# ADC_2CH.net
KiCad netlist of a schematic drawn in Altium Designer
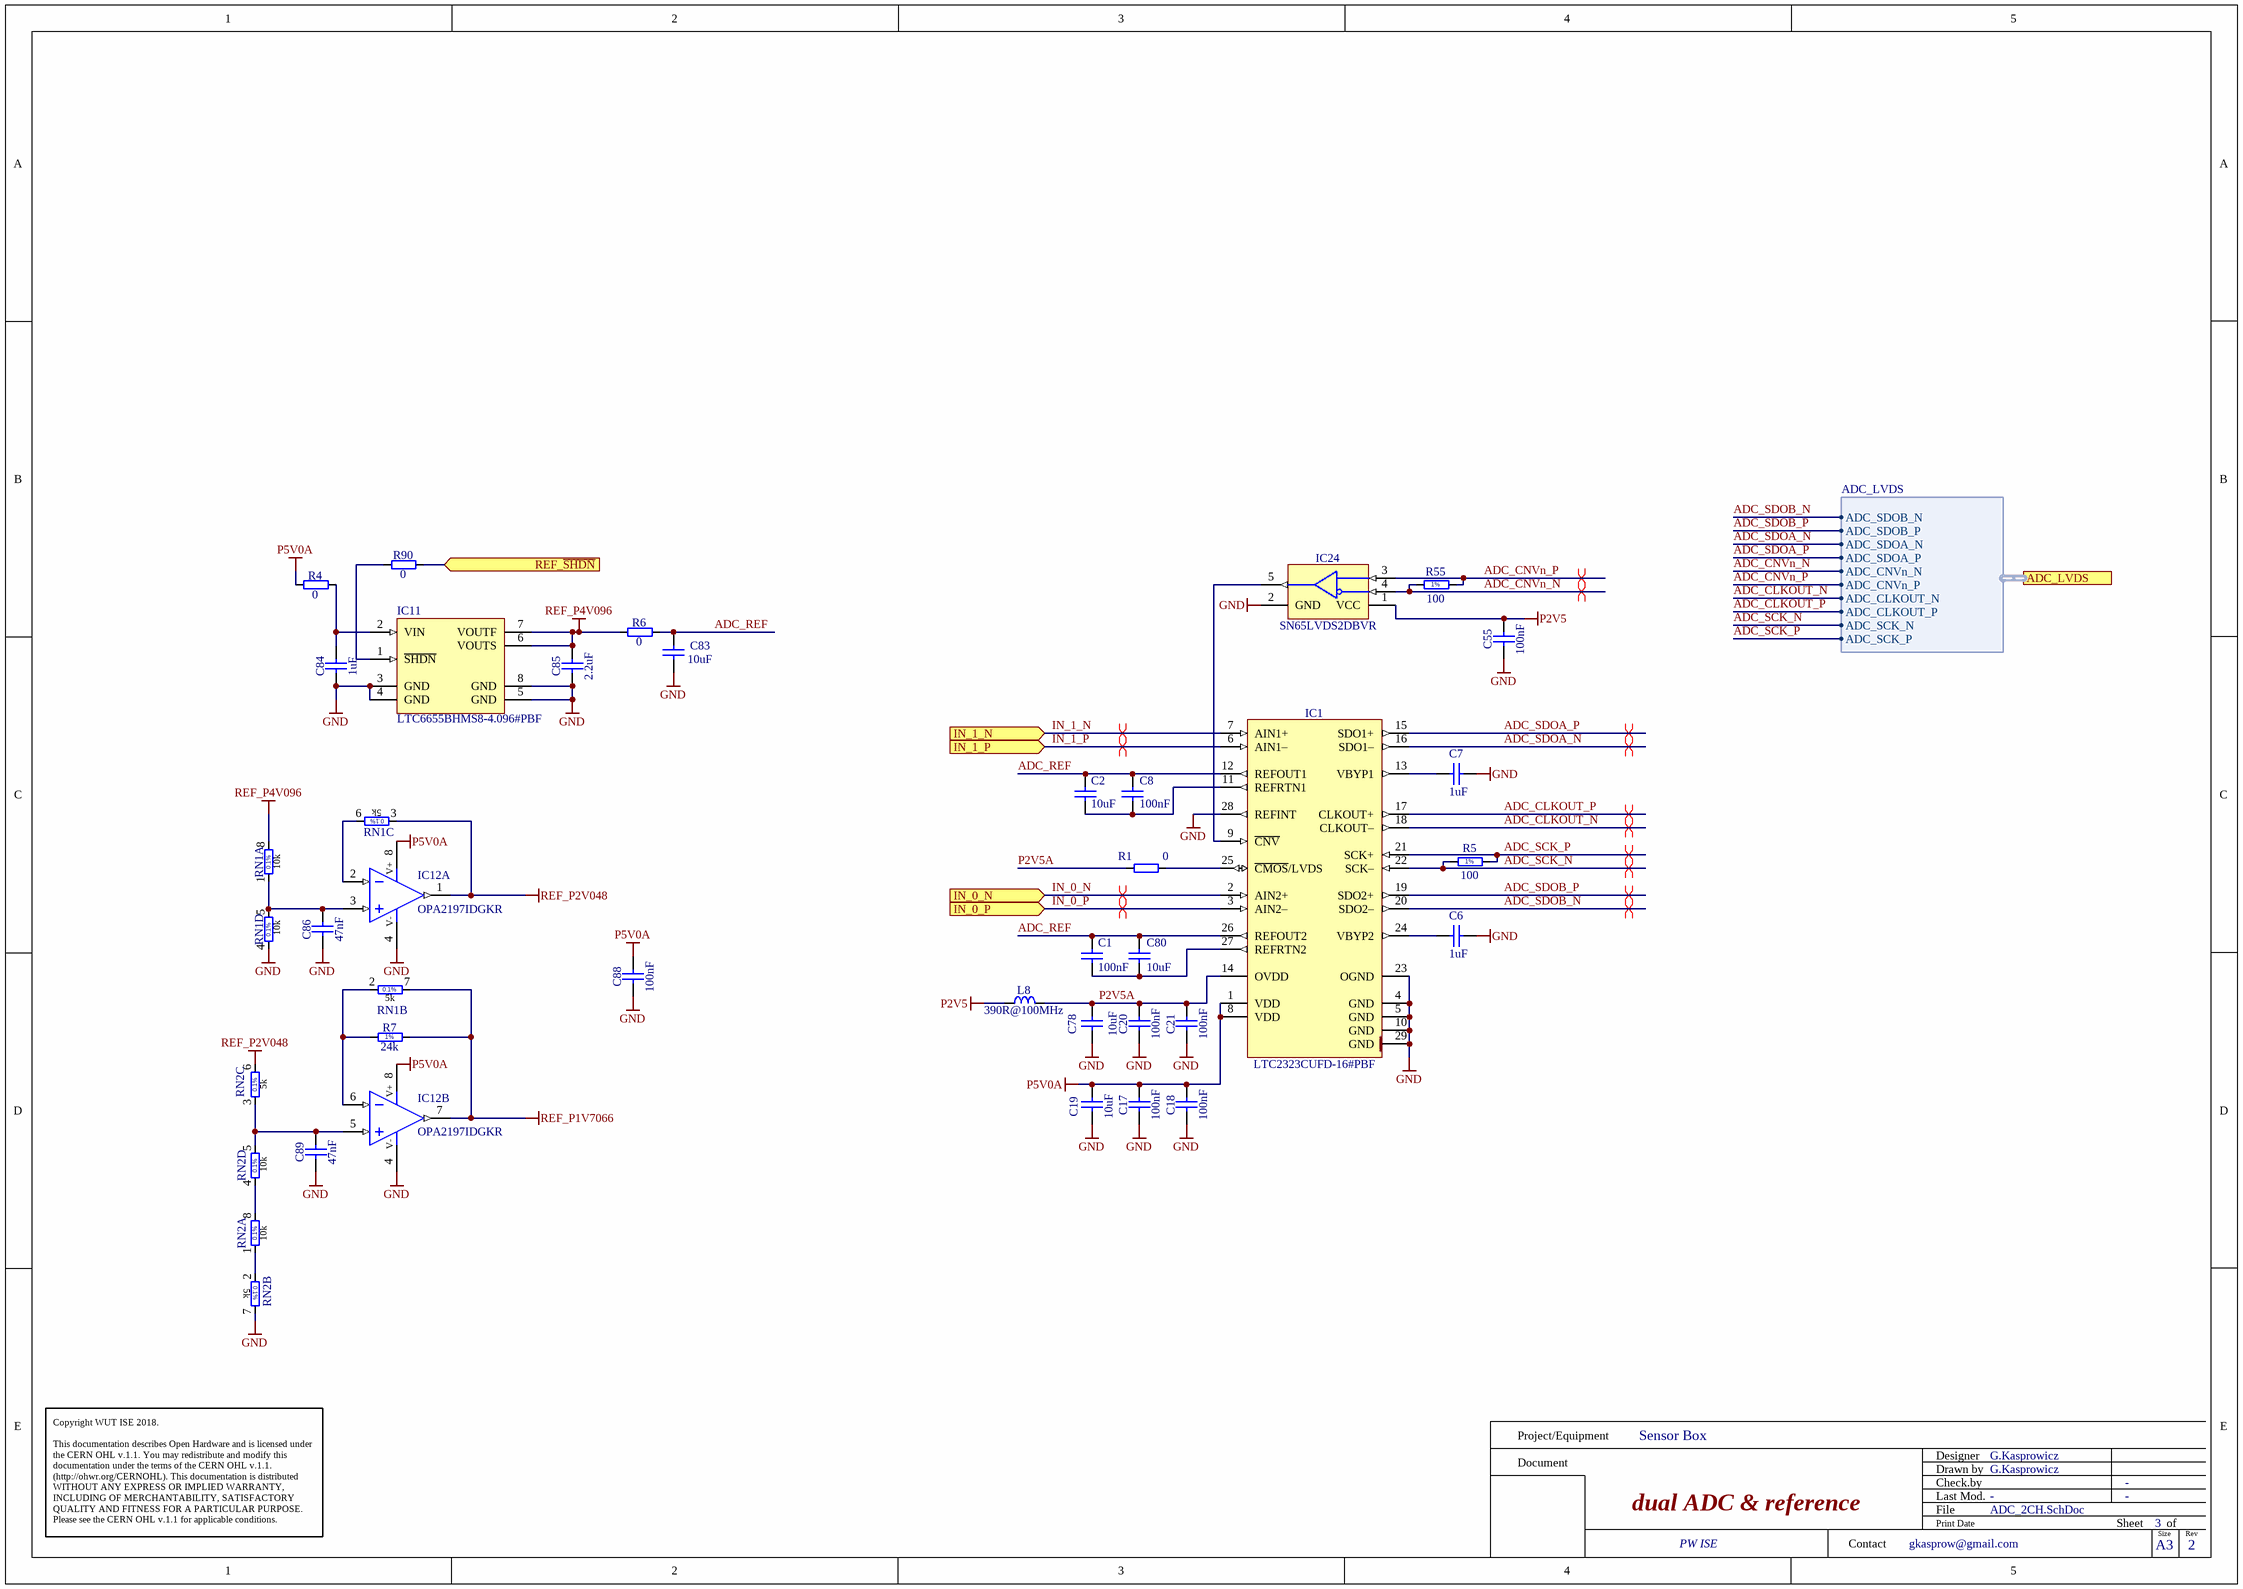
[diagram p0: ADC_2CH.SchDoc]

(export (version "E")
  (design (tool "Eeschema 10.0.6"))
  (components
    (comp (ref "C1")
      (value "100nF")
      (footprint "CAPC1608X87N")
      (description "Non-polarised capacitor")
      (fields
        (field (name "PART NUMBER") "CC0603_100NF_50V_10%_X7R")
        (field (name "VOLTAGE") "50V")
        (field (name "AUTHOR") "CERN DEM JLC")
      )
      (libsource (lib "Capacitors") (part "Capacitor - non polarized"))
    )
    (comp (ref "C2")
      (value "10uF")
      (footprint "CAPC2012X95N")
      (description "Non-polarised capacitor")
      (fields
        (field (name "PART NUMBER") "CC0805_10UF_25V_10%_X5R")
        (field (name "VOLTAGE") "25V")
        (field (name "AUTHOR") "CERN DEM JLC")
      )
      (libsource (lib "Capacitors") (part "Capacitor - non polarized"))
    )
    (comp (ref "C6")
      (value "1uF")
      (footprint "CAPC1608X87N")
      (description "Non-polarised capacitor")
      (fields
        (field (name "PART NUMBER") "CC0603_1UF_25V_10%_X7R")
        (field (name "VOLTAGE") "25V")
        (field (name "AUTHOR") "CERN DEM JLC")
      )
      (libsource (lib "Capacitors") (part "Capacitor - non polarized"))
    )
    (comp (ref "C7")
      (value "1uF")
      (footprint "CAPC1608X87N")
      (description "Non-polarised capacitor")
      (fields
        (field (name "PART NUMBER") "CC0603_1UF_25V_10%_X7R")
        (field (name "VOLTAGE") "25V")
        (field (name "AUTHOR") "CERN DEM JLC")
      )
      (libsource (lib "Capacitors") (part "Capacitor - non polarized"))
    )
    (comp (ref "C8")
      (value "100nF")
      (footprint "CAPC1608X87N")
      (description "Non-polarised capacitor")
      (fields
        (field (name "PART NUMBER") "CC0603_100NF_50V_10%_X7R")
        (field (name "VOLTAGE") "50V")
        (field (name "AUTHOR") "CERN DEM JLC")
      )
      (libsource (lib "Capacitors") (part "Capacitor - non polarized"))
    )
    (comp (ref "C17")
      (value "100nF")
      (footprint "CAPC1608X87N")
      (description "Non-polarised capacitor")
      (fields
        (field (name "PART NUMBER") "CC0603_100NF_50V_10%_X7R")
        (field (name "VOLTAGE") "50V")
        (field (name "AUTHOR") "CERN DEM JLC")
      )
      (libsource (lib "Capacitors") (part "Capacitor - non polarized"))
    )
    (comp (ref "C18")
      (value "100nF")
      (footprint "CAPC1608X87N")
      (description "Non-polarised capacitor")
      (fields
        (field (name "PART NUMBER") "CC0603_100NF_50V_10%_X7R")
        (field (name "VOLTAGE") "50V")
        (field (name "AUTHOR") "CERN DEM JLC")
      )
      (libsource (lib "Capacitors") (part "Capacitor - non polarized"))
    )
    (comp (ref "C19")
      (value "10uF")
      (footprint "CAPC2012X95N")
      (description "Non-polarised capacitor")
      (fields
        (field (name "PART NUMBER") "CC0805_10UF_25V_10%_X5R")
        (field (name "VOLTAGE") "25V")
        (field (name "AUTHOR") "CERN DEM JLC")
      )
      (libsource (lib "Capacitors") (part "Capacitor - non polarized"))
    )
    (comp (ref "C20")
      (value "100nF")
      (footprint "CAPC1608X87N")
      (description "Non-polarised capacitor")
      (fields
        (field (name "PART NUMBER") "CC0603_100NF_50V_10%_X7R")
        (field (name "VOLTAGE") "50V")
        (field (name "AUTHOR") "CERN DEM JLC")
      )
      (libsource (lib "Capacitors") (part "Capacitor - non polarized"))
    )
    (comp (ref "C21")
      (value "100nF")
      (footprint "CAPC1608X87N")
      (description "Non-polarised capacitor")
      (fields
        (field (name "PART NUMBER") "CC0603_100NF_50V_10%_X7R")
        (field (name "VOLTAGE") "50V")
        (field (name "AUTHOR") "CERN DEM JLC")
      )
      (libsource (lib "Capacitors") (part "Capacitor - non polarized"))
    )
    (comp (ref "C55")
      (value "100nF")
      (footprint "CAPC1608X87N")
      (description "Non-polarised capacitor")
      (fields
        (field (name "PART NUMBER") "CC0603_100NF_50V_10%_X7R")
        (field (name "VOLTAGE") "50V")
        (field (name "AUTHOR") "CERN DEM JLC")
      )
      (libsource (lib "Capacitors") (part "Capacitor - non polarized"))
    )
    (comp (ref "C78")
      (value "10uF")
      (footprint "CAPC2012X95N")
      (description "Non-polarised capacitor")
      (fields
        (field (name "PART NUMBER") "CC0805_10UF_25V_10%_X5R")
        (field (name "VOLTAGE") "25V")
        (field (name "AUTHOR") "CERN DEM JLC")
      )
      (libsource (lib "Capacitors") (part "Capacitor - non polarized"))
    )
    (comp (ref "C80")
      (value "10uF")
      (footprint "CAPC2012X95N")
      (description "Non-polarised capacitor")
      (fields
        (field (name "PART NUMBER") "CC0805_10UF_25V_10%_X5R")
        (field (name "VOLTAGE") "25V")
        (field (name "AUTHOR") "CERN DEM JLC")
      )
      (libsource (lib "Capacitors") (part "Capacitor - non polarized"))
    )
    (comp (ref "C83")
      (value "10uF")
      (footprint "CAPC2012X95N")
      (description "Non-polarised capacitor")
      (fields
        (field (name "PART NUMBER") "CC0805_10UF_25V_10%_X5R")
        (field (name "VOLTAGE") "25V")
        (field (name "AUTHOR") "CERN DEM JLC")
      )
      (libsource (lib "Capacitors") (part "Capacitor - non polarized"))
    )
    (comp (ref "C84")
      (value "1uF")
      (footprint "CAPC1608X87N")
      (description "Non-polarised capacitor")
      (fields
        (field (name "PART NUMBER") "CC0603_1UF_25V_10%_X7R")
        (field (name "VOLTAGE") "25V")
        (field (name "AUTHOR") "CERN DEM JLC")
      )
      (libsource (lib "Capacitors") (part "Capacitor - non polarized"))
    )
    (comp (ref "C85")
      (value "2.2uF")
      (footprint "CAPC1608X87N")
      (description "Non-polarised capacitor")
      (fields
        (field (name "PART NUMBER") "CC0603_2.2UF_16V_10%_X5R")
        (field (name "VOLTAGE") "16V")
        (field (name "AUTHOR") "CERN DEM JLC")
      )
      (libsource (lib "Capacitors") (part "Capacitor - non polarized"))
    )
    (comp (ref "C86")
      (value "47nF")
      (footprint "CAPC2012X135N")
      (description "Non-polarised capacitor")
      (fields
        (field (name "PART NUMBER") "CC0805_47NF_25V_5%_C0G")
        (field (name "VOLTAGE") "25V")
        (field (name "AUTHOR") "CERN DEM JLC")
      )
      (libsource (lib "Capacitors") (part "Capacitor - non polarized"))
    )
    (comp (ref "C88")
      (value "100nF")
      (footprint "CAPC1005X55N")
      (description "Non-polarised capacitor")
      (fields
        (field (name "PART NUMBER") "CC0402_100NF_16V_10%_X5R")
        (field (name "VOLTAGE") "16V")
        (field (name "AUTHOR") "CERN DEM JLC")
      )
      (libsource (lib "Capacitors") (part "Capacitor - non polarized"))
    )
    (comp (ref "C89")
      (value "47nF")
      (footprint "CAPC2012X135N")
      (description "Non-polarised capacitor")
      (fields
        (field (name "PART NUMBER") "CC0805_47NF_25V_5%_C0G")
        (field (name "VOLTAGE") "25V")
        (field (name "AUTHOR") "CERN DEM JLC")
      )
      (libsource (lib "Capacitors") (part "Capacitor - non polarized"))
    )
    (comp (ref "IC1")
      (value "LTC2323CUFD-16#PBF")
      (footprint "QFN50P400X500X80-29N-R275X375")
      (description "Dual, 16-Bit, 5Msps Differential Input ADC with Wide Input Common Mode Range")
      (fields (field (name "MANUFACTURER") "ANALOG DEVICES") (field (name "AUTHOR") "CERN DEM JMW"))
      (libsource (lib "ICs And Semiconductors") (part "LTC2323-16"))
    )
    (comp (ref "IC11")
      (value "LTC6655BHMS8-4.096#PBF")
      (footprint "SOP65P490X110-8N")
      (description "0.25ppm Noise, Low Drift Precision Buffered Voltage Reference")
      (fields (field (name "MANUFACTURER") "LINEAR TECHNOLOGY") (field (name "AUTHOR") "GK"))
      (libsource (lib "LIBRARY_SCH") (part "REF_LTC6655"))
    )
    (comp (ref "IC12")
      (value "OPA2197IDGKR")
      (footprint "SOP65P490X110-8N")
      (description "36-V, Precision, Rail-to-Rail Input Output, Low Offset Voltage Op Amp 8-VSSOP")
      (fields (field (name "MANUFACTURER") "TEXAS INSTRUMENTS") (field (name "AUTHOR") "GK"))
      (libsource (lib "LIBRARY_SCH") (part "OA_OPA2197IDGKR"))
    )
    (comp (ref "IC24")
      (value "SN65LVDS2DBVR")
      (footprint "SOT95P280X145-5N")
      (description "High-Speed Differential Line Receiver")
      (fields (field (name "MANUFACTURER") "TEXAS INSTRUMENTS") (field (name "AUTHOR") "CERN DEM JLC"))
      (libsource (lib "ICs And Semiconductors") (part "SN65LVDS2DBV"))
    )
    (comp (ref "L8")
      (value "390R@100MHz")
      (footprint "INDC1608X95N")
      (description "Inductor")
      (fields
        (field (name "PART NUMBER") "IND0603_TDK_MPZ1608R391A")
        (field (name "POWER") "1.2A")
        (field (name "AUTHOR") "CERN DEM JLC")
      )
      (libsource (lib "Inductors & Transformers") (part "Inductor"))
    )
    (comp (ref "R1")
      (value "0")
      (footprint "RESC1005X40N")
      (description "Resistor")
      (fields
        (field (name "PART NUMBER") "R0402_0R_JUMPER")
        (field (name "MANUFACTURER") "GENERIC")
        (field (name "AUTHOR") "CERN DEM JLC")
      )
      (libsource (lib "Resistors") (part "Resistor"))
    )
    (comp (ref "R4")
      (value "0")
      (footprint "RESC1005X40N")
      (description "Resistor")
      (fields
        (field (name "PART NUMBER") "R0402_0R_JUMPER")
        (field (name "MANUFACTURER") "GENERIC")
        (field (name "AUTHOR") "CERN DEM JLC")
      )
      (libsource (lib "Resistors") (part "Resistor"))
    )
    (comp (ref "R5")
      (value "100")
      (footprint "RESC1005X40N")
      (description "Resistor - 1%")
      (fields
        (field (name "PART NUMBER") "R0402_100R_1%_0.1W_100PPM")
        (field (name "POWER") "0.1W")
        (field (name "AUTHOR") "CERN DEM JLC")
      )
      (libsource (lib "Resistors") (part "Resistor - 1%"))
    )
    (comp (ref "R6")
      (value "0")
      (footprint "RESC1005X40N")
      (description "Resistor")
      (fields
        (field (name "PART NUMBER") "R0402_0R_JUMPER")
        (field (name "MANUFACTURER") "GENERIC")
        (field (name "AUTHOR") "CERN DEM JLC")
      )
      (libsource (lib "Resistors") (part "Resistor"))
    )
    (comp (ref "R7")
      (value "24k")
      (footprint "RESC1608X55N")
      (description "Resistor - 1%")
      (fields
        (field (name "PART NUMBER") "R0603_24K_1%_0.1W_100PPM")
        (field (name "POWER") "0.1W")
        (field (name "AUTHOR") "CERN DEM JLC")
      )
      (libsource (lib "Resistors") (part "Resistor - 1%"))
    )
    (comp (ref "R55")
      (value "100")
      (footprint "RESC1005X40N")
      (description "Resistor - 1%")
      (fields
        (field (name "PART NUMBER") "R0402_100R_1%_0.1W_100PPM")
        (field (name "POWER") "0.1W")
        (field (name "AUTHOR") "CERN DEM JLC")
      )
      (libsource (lib "Resistors") (part "Resistor - 1%"))
    )
    (comp (ref "R90")
      (value "0")
      (footprint "RESC1005X40N")
      (description "Resistor")
      (fields
        (field (name "PART NUMBER") "R0402_0R_JUMPER")
        (field (name "MANUFACTURER") "GENERIC")
        (field (name "AUTHOR") "CERN DEM JLC")
      )
      (libsource (lib "Resistors") (part "Resistor"))
    )
    (comp (ref "RN1")
      (value "10k 5K 5K 10K")
      (footprint "SOIC127P600X175-8N")
      (description "DIL8 Resistor Network 4 Resistors 10k-5k-5k-10k 0.1%")
      (fields
        (field (name "PART NUMBER") "RN_10K_5K_VISHAY_AORN2-1AT3")
        (field (name "POWER") "4x0.1W")
        (field (name "AUTHOR") "CERN DEM JLC")
      )
      (libsource (lib "Resistors") (part "RN DIL8_4xR_10k-5k-5k-10k_0.1%"))
    )
    (comp (ref "RN2")
      (value "10k 5K 5K 10K")
      (footprint "SOIC127P600X175-8N")
      (description "DIL8 Resistor Network 4 Resistors 10k-5k-5k-10k 0.1%")
      (fields
        (field (name "PART NUMBER") "RN_10K_5K_VISHAY_AORN2-1AT3")
        (field (name "POWER") "4x0.1W")
        (field (name "AUTHOR") "CERN DEM JLC")
      )
      (libsource (lib "Resistors") (part "RN DIL8_4xR_10k-5k-5k-10k_0.1%"))
    )
  )
  (nets
    (net (code "2") (name "/ADC_CLKOUT_N") (class "Default")
      (node (ref "IC1") (pin "18") (pinfunction "CLKOUT–_18") (pintype "output"))
    )
    (net (code "3") (name "/ADC_CLKOUT_P") (class "Default")
      (node (ref "IC1") (pin "17") (pinfunction "CLKOUT+_17") (pintype "output"))
    )
    (net (code "4") (name "/ADC_CNVn_N") (class "Default")
      (node (ref "IC24") (pin "4") (pinfunction "B_4") (pintype "input"))
      (node (ref "R55") (pin "1") (pinfunction "1_1") (pintype "passive"))
    )
    (net (code "5") (name "/ADC_CNVn_P") (class "Default")
      (node (ref "IC24") (pin "3") (pinfunction "A_3") (pintype "input"))
      (node (ref "R55") (pin "2") (pinfunction "2_2") (pintype "passive"))
    )
    (net (code "6") (name "/ADC_REF") (class "Default")
      (node (ref "C1") (pin "1") (pinfunction "1_1") (pintype "passive"))
      (node (ref "C2") (pin "2") (pinfunction "2_2") (pintype "passive"))
      (node (ref "C8") (pin "1") (pinfunction "1_1") (pintype "passive"))
      (node (ref "C80") (pin "2") (pinfunction "2_2") (pintype "passive"))
      (node (ref "C83") (pin "2") (pinfunction "2_2") (pintype "passive"))
      (node (ref "IC1") (pin "12") (pinfunction "REFOUT1_12") (pintype "output"))
      (node (ref "IC1") (pin "26") (pinfunction "REFOUT2_26") (pintype "output"))
      (node (ref "R6") (pin "2") (pinfunction "2_2") (pintype "passive"))
    )
    (net (code "7") (name "/ADC_SCK_N") (class "Default")
      (node (ref "IC1") (pin "22") (pinfunction "SCK–_22") (pintype "input"))
      (node (ref "R5") (pin "1") (pinfunction "1_1") (pintype "passive"))
    )
    (net (code "8") (name "/ADC_SCK_P") (class "Default")
      (node (ref "IC1") (pin "21") (pinfunction "SCK+_21") (pintype "input"))
      (node (ref "R5") (pin "2") (pinfunction "2_2") (pintype "passive"))
    )
    (net (code "9") (name "/ADC_SDOA_N") (class "Default")
      (node (ref "IC1") (pin "16") (pinfunction "SDO1–_16") (pintype "output"))
    )
    (net (code "10") (name "/ADC_SDOA_P") (class "Default")
      (node (ref "IC1") (pin "15") (pinfunction "SDO1+_15") (pintype "output"))
    )
    (net (code "11") (name "/ADC_SDOB_N") (class "Default")
      (node (ref "IC1") (pin "20") (pinfunction "SDO2–_20") (pintype "output"))
    )
    (net (code "12") (name "/ADC_SDOB_P") (class "Default")
      (node (ref "IC1") (pin "19") (pinfunction "SDO2+_19") (pintype "output"))
    )
    (net (code "13") (name "/IN_0_N") (class "Default")
      (node (ref "IC1") (pin "2") (pinfunction "AIN2+_2") (pintype "input"))
    )
    (net (code "14") (name "/IN_0_P") (class "Default")
      (node (ref "IC1") (pin "3") (pinfunction "AIN2–_3") (pintype "input"))
    )
    (net (code "15") (name "/IN_1_N") (class "Default")
      (node (ref "IC1") (pin "7") (pinfunction "AIN1+_7") (pintype "input"))
    )
    (net (code "16") (name "/IN_1_P") (class "Default")
      (node (ref "IC1") (pin "6") (pinfunction "AIN1–_6") (pintype "input"))
    )
    (net (code "17") (name "/P2V5A") (class "Default")
      (node (ref "C20") (pin "2") (pinfunction "2_2") (pintype "passive"))
      (node (ref "C21") (pin "2") (pinfunction "2_2") (pintype "passive"))
      (node (ref "C78") (pin "2") (pinfunction "2_2") (pintype "passive"))
      (node (ref "IC1") (pin "14") (pinfunction "OVDD_14") (pintype "power_in"))
      (node (ref "L8") (pin "1") (pinfunction "1_1") (pintype "passive"))
      (node (ref "R1") (pin "2") (pinfunction "2_2") (pintype "passive"))
    )
    (net (code "18") (name "/REF_~{SHDN}") (class "Default")
      (node (ref "R90") (pin "2") (pinfunction "2_2") (pintype "passive"))
    )
    (net (code "20") (name "GND") (class "Default")
      (node (ref "C17") (pin "1") (pinfunction "1_1") (pintype "passive"))
      (node (ref "C18") (pin "1") (pinfunction "1_1") (pintype "passive"))
      (node (ref "C19") (pin "1") (pinfunction "1_1") (pintype "passive"))
      (node (ref "C20") (pin "1") (pinfunction "1_1") (pintype "passive"))
      (node (ref "C21") (pin "1") (pinfunction "1_1") (pintype "passive"))
      (node (ref "C55") (pin "1") (pinfunction "1_1") (pintype "passive"))
      (node (ref "C6") (pin "1") (pinfunction "1_1") (pintype "passive"))
      (node (ref "C7") (pin "1") (pinfunction "1_1") (pintype "passive"))
      (node (ref "C78") (pin "1") (pinfunction "1_1") (pintype "passive"))
      (node (ref "C83") (pin "1") (pinfunction "1_1") (pintype "passive"))
      (node (ref "C84") (pin "1") (pinfunction "1_1") (pintype "passive"))
      (node (ref "C85") (pin "1") (pinfunction "1_1") (pintype "passive"))
      (node (ref "C86") (pin "1") (pinfunction "1_1") (pintype "passive"))
      (node (ref "C88") (pin "1") (pinfunction "1_1") (pintype "passive"))
      (node (ref "C89") (pin "1") (pinfunction "1_1") (pintype "passive"))
      (node (ref "IC1") (pin "10") (pinfunction "GND_10") (pintype "power_in"))
      (node (ref "IC1") (pin "23") (pinfunction "OGND_23") (pintype "power_in"))
      (node (ref "IC1") (pin "28") (pinfunction "REFINT_28") (pintype "output"))
      (node (ref "IC1") (pin "29") (pinfunction "GND_29") (pintype "power_in"))
      (node (ref "IC1") (pin "4") (pinfunction "GND_4") (pintype "power_in"))
      (node (ref "IC1") (pin "5") (pinfunction "GND_5") (pintype "power_in"))
      (node (ref "IC11") (pin "3") (pinfunction "GND_3") (pintype "power_in"))
      (node (ref "IC11") (pin "4") (pinfunction "GND_4") (pintype "power_in"))
      (node (ref "IC11") (pin "5") (pinfunction "GND_5") (pintype "power_in"))
      (node (ref "IC11") (pin "8") (pinfunction "GND_8") (pintype "power_in"))
      (node (ref "IC12") (pin "4") (pinfunction "V-_4") (pintype "power_in"))
      (node (ref "IC24") (pin "2") (pinfunction "GND_2") (pintype "power_in"))
      (node (ref "RN1") (pin "4") (pinfunction "4_4") (pintype "passive"))
      (node (ref "RN2") (pin "7") (pinfunction "7_7") (pintype "passive"))
    )
    (net (code "21") (name "Net-(IC1-REFRTN1)") (class "Default")
      (node (ref "C2") (pin "1") (pinfunction "1_1") (pintype "passive"))
      (node (ref "C8") (pin "2") (pinfunction "2_2") (pintype "passive"))
      (node (ref "IC1") (pin "11") (pinfunction "REFRTN1_11") (pintype "output"))
    )
    (net (code "22") (name "Net-(IC1-REFRTN2)") (class "Default")
      (node (ref "C1") (pin "2") (pinfunction "2_2") (pintype "passive"))
      (node (ref "C80") (pin "1") (pinfunction "1_1") (pintype "passive"))
      (node (ref "IC1") (pin "27") (pinfunction "REFRTN2_27") (pintype "output"))
    )
    (net (code "23") (name "Net-(IC1-VBYP1)") (class "Default")
      (node (ref "C7") (pin "2") (pinfunction "2_2") (pintype "passive"))
      (node (ref "IC1") (pin "13") (pinfunction "VBYP1_13") (pintype "output"))
    )
    (net (code "24") (name "Net-(IC1-VBYP2)") (class "Default")
      (node (ref "C6") (pin "2") (pinfunction "2_2") (pintype "passive"))
      (node (ref "IC1") (pin "24") (pinfunction "VBYP2_24") (pintype "output"))
    )
    (net (code "25") (name "Net-(IC1-~{CMOS}{slash}LVDS)") (class "Default")
      (node (ref "IC1") (pin "25") (pinfunction "~{CMOS}/LVDS_25") (pintype "bidirectional"))
      (node (ref "R1") (pin "1") (pinfunction "1_1") (pintype "passive"))
    )
    (net (code "26") (name "Net-(IC1-~{CNV})") (class "Default")
      (node (ref "IC1") (pin "9") (pinfunction "~{CNV}_9") (pintype "input"))
      (node (ref "IC24") (pin "5") (pinfunction "R_5") (pintype "output"))
    )
    (net (code "27") (name "Net-(IC11-VIN)") (class "Default")
      (node (ref "C84") (pin "2") (pinfunction "2_2") (pintype "passive"))
      (node (ref "IC11") (pin "2") (pinfunction "VIN_2") (pintype "input"))
      (node (ref "R4") (pin "2") (pinfunction "2_2") (pintype "passive"))
    )
    (net (code "28") (name "Net-(IC11-~{SHDN})") (class "Default")
      (node (ref "IC11") (pin "1") (pinfunction "~{SHDN}_1") (pintype "input"))
      (node (ref "R90") (pin "1") (pinfunction "1_1") (pintype "passive"))
    )
    (net (code "29") (name "Net-(IC12A-IN+)") (class "Default")
      (node (ref "C86") (pin "2") (pinfunction "2_2") (pintype "passive"))
      (node (ref "IC12") (pin "3") (pinfunction "IN+_3") (pintype "input"))
      (node (ref "RN1") (pin "1") (pinfunction "1_1") (pintype "passive"))
      (node (ref "RN1") (pin "5") (pinfunction "5_5") (pintype "passive"))
    )
    (net (code "30") (name "Net-(IC12A-IN-)") (class "Default")
      (node (ref "IC12") (pin "2") (pinfunction "IN-_2") (pintype "input"))
      (node (ref "RN1") (pin "6") (pinfunction "6_6") (pintype "passive"))
    )
    (net (code "31") (name "Net-(IC12B-IN+)") (class "Default")
      (node (ref "C89") (pin "2") (pinfunction "2_2") (pintype "passive"))
      (node (ref "IC12") (pin "5") (pinfunction "IN+_5") (pintype "input"))
      (node (ref "RN2") (pin "3") (pinfunction "3_3") (pintype "passive"))
      (node (ref "RN2") (pin "5") (pinfunction "5_5") (pintype "passive"))
    )
    (net (code "32") (name "Net-(IC12B-IN-)") (class "Default")
      (node (ref "IC12") (pin "6") (pinfunction "IN-_6") (pintype "input"))
      (node (ref "R7") (pin "1") (pinfunction "1_1") (pintype "passive"))
      (node (ref "RN1") (pin "2") (pinfunction "2_2") (pintype "passive"))
    )
    (net (code "33") (name "Net-(RN2-Pad1)") (class "Default")
      (node (ref "RN2") (pin "1") (pinfunction "1_1") (pintype "passive"))
      (node (ref "RN2") (pin "2") (pinfunction "2_2") (pintype "passive"))
    )
    (net (code "34") (name "Net-(RN2-Pad4)") (class "Default")
      (node (ref "RN2") (pin "4") (pinfunction "4_4") (pintype "passive"))
      (node (ref "RN2") (pin "8") (pinfunction "8_8") (pintype "passive"))
    )
    (net (code "35") (name "P2V5") (class "Default")
      (node (ref "C55") (pin "2") (pinfunction "2_2") (pintype "passive"))
      (node (ref "IC24") (pin "1") (pinfunction "VCC_1") (pintype "power_in"))
      (node (ref "L8") (pin "2") (pinfunction "2_2") (pintype "passive"))
    )
    (net (code "36") (name "P5V0A") (class "Default")
      (node (ref "C17") (pin "2") (pinfunction "2_2") (pintype "passive"))
      (node (ref "C18") (pin "2") (pinfunction "2_2") (pintype "passive"))
      (node (ref "C19") (pin "2") (pinfunction "2_2") (pintype "passive"))
      (node (ref "C88") (pin "2") (pinfunction "2_2") (pintype "passive"))
      (node (ref "IC1") (pin "1") (pinfunction "VDD_1") (pintype "power_in"))
      (node (ref "IC1") (pin "8") (pinfunction "VDD_8") (pintype "power_in"))
      (node (ref "IC12") (pin "8") (pinfunction "V+_8") (pintype "power_in"))
      (node (ref "R4") (pin "1") (pinfunction "1_1") (pintype "passive"))
    )
    (net (code "37") (name "REF_P1V7066") (class "Default")
      (node (ref "IC12") (pin "7") (pinfunction "OUT_7") (pintype "output"))
      (node (ref "R7") (pin "2") (pinfunction "2_2") (pintype "passive"))
      (node (ref "RN1") (pin "7") (pinfunction "7_7") (pintype "passive"))
    )
    (net (code "38") (name "REF_P2V048") (class "Default")
      (node (ref "IC12") (pin "1") (pinfunction "OUT_1") (pintype "output"))
      (node (ref "RN1") (pin "3") (pinfunction "3_3") (pintype "passive"))
      (node (ref "RN2") (pin "6") (pinfunction "6_6") (pintype "passive"))
    )
    (net (code "39") (name "REF_P4V096") (class "Default")
      (node (ref "C85") (pin "2") (pinfunction "2_2") (pintype "passive"))
      (node (ref "IC11") (pin "6") (pinfunction "VOUTS_6") (pintype "power_in"))
      (node (ref "IC11") (pin "7") (pinfunction "VOUTF_7") (pintype "power_in"))
      (node (ref "R6") (pin "1") (pinfunction "1_1") (pintype "passive"))
      (node (ref "RN1") (pin "8") (pinfunction "8_8") (pintype "passive"))
    )
  )
)
